# ProPrj___2025-12-14-15-46-23.net
KiCad netlist of a schematic drawn in EasyEDA Pro
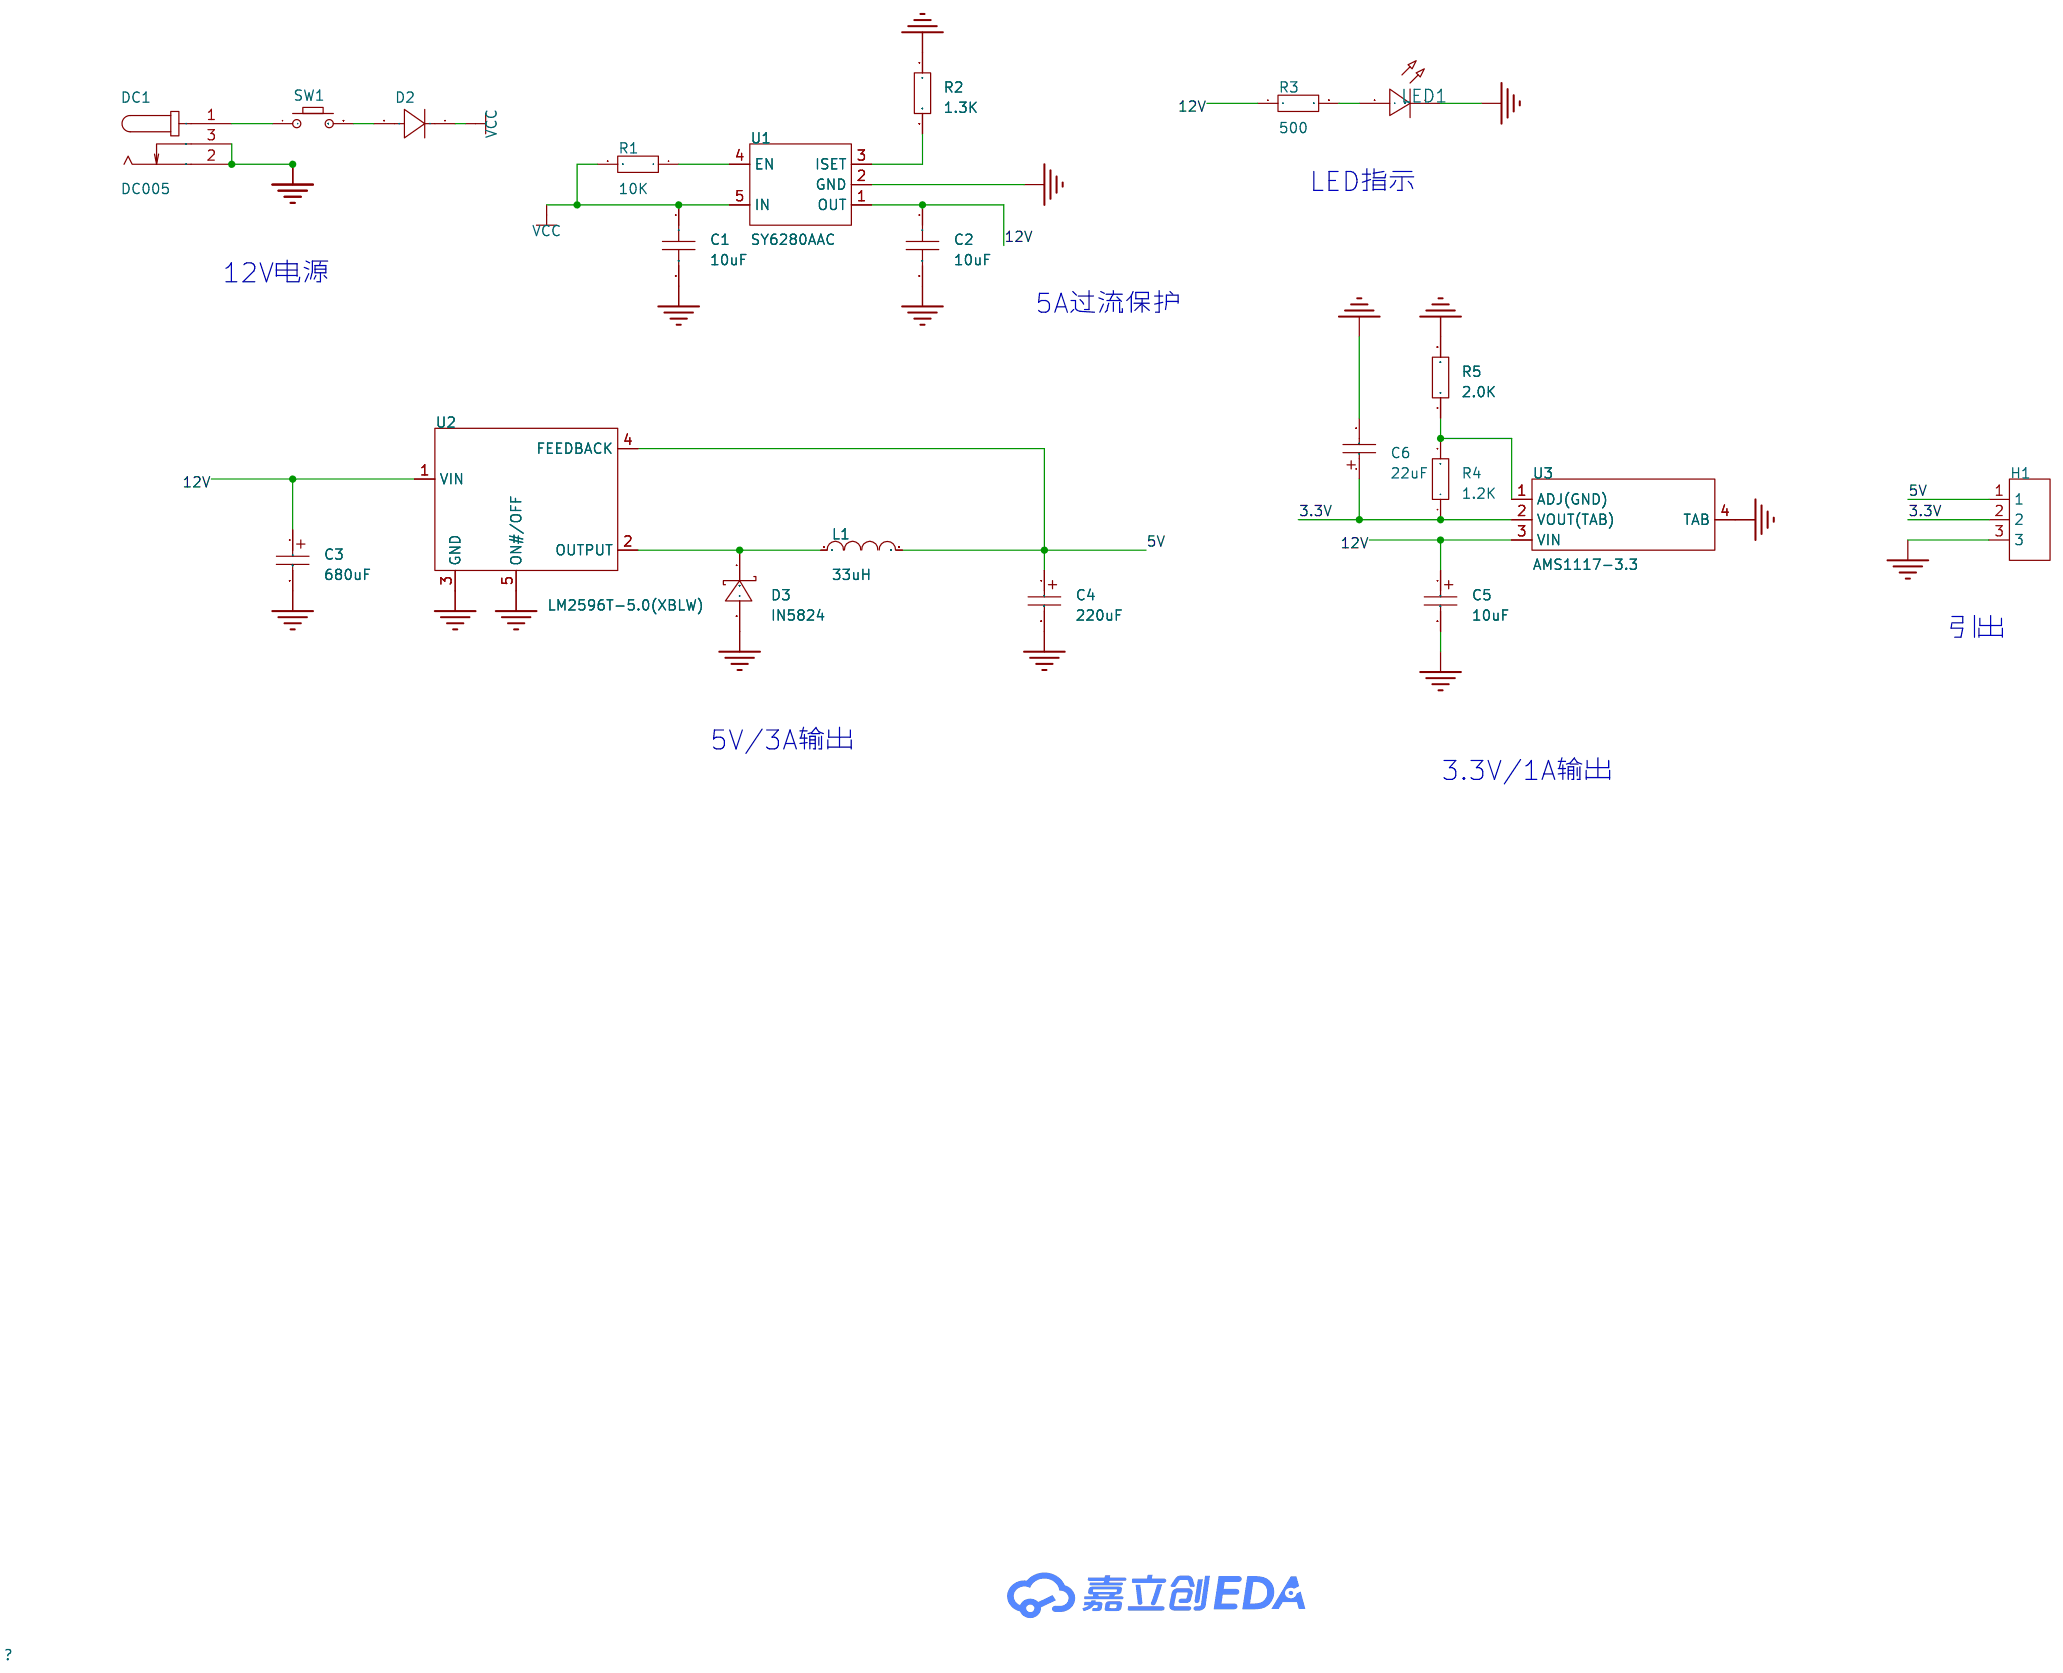
[diagram p0: schematic sheet]

(export (version "E")
  (design (tool "Eeschema 10.0.6"))
  (components
    (comp (ref "C1")
      (value "10uF")
      (footprint "easyedapro:C0603")
      (libsource (lib "easyedapro") (part "Capacitance"))
    )
    (comp (ref "C2")
      (value "10uF")
      (footprint "easyedapro:C0603")
      (libsource (lib "easyedapro") (part "Capacitance"))
    )
    (comp (ref "C3")
      (value "680uF")
      (footprint "easyedapro:C_Ele_SMD_3x5.4mm")
      (libsource (lib "easyedapro") (part "CAP"))
    )
    (comp (ref "C4")
      (value "220uF")
      (footprint "easyedapro:C_Ele_SMD_3x5.4mm")
      (libsource (lib "easyedapro") (part "CAP"))
    )
    (comp (ref "C5")
      (value "10uF")
      (footprint "easyedapro:C_Ele_SMD_3x5.4mm")
      (libsource (lib "easyedapro") (part "CAP"))
    )
    (comp (ref "C6")
      (value "22uF")
      (footprint "easyedapro:C_Ele_SMD_3x5.4mm")
      (libsource (lib "easyedapro") (part "CAP"))
    )
    (comp (ref "D2")
      (value "~")
      (footprint "easyedapro:DO_1N4007")
      (libsource (lib "easyedapro") (part "D_1N4007"))
    )
    (comp (ref "D3")
      (value "IN5824")
      (footprint "easyedapro:SMAF_L3.5-W2.6-LS4.7-RD")
      (libsource (lib "easyedapro") (part "IN5824"))
    )
    (comp (ref "DC1")
      (value "DC005")
      (footprint "easyedapro:DC-IN-TH_DC005")
      (description "连接器类型:DC电源插座;安装方式:弯插;触点内径:2mm;触点外径:6.3mm;额定电流:500mA;额定电压:12V;工作温度:-30°C~+70°C;")
      (fields (field (name "Manufacturer") "SHOU HAN(首韩)"))
      (libsource (lib "easyedapro") (part "DC005_C431533"))
    )
    (comp (ref "H1")
      (value "~")
      (footprint "easyedapro:HDR-TH_3P-P2.54-V-F")
      (libsource (lib "easyedapro") (part "PM254V-11-03-H85"))
    )
    (comp (ref "L1")
      (value "33uH")
      (footprint "easyedapro:L0603")
      (libsource (lib "easyedapro") (part "SDFL1608S100KTF"))
    )
    (comp (ref "LED1")
      (value "~")
      (footprint "easyedapro:LED_0603")
      (libsource (lib "easyedapro") (part "LED_R"))
    )
    (comp (ref "R1") (value "10K") (footprint "easyedapro:R0603") (libsource (lib "easyedapro") (part "电阻")))
    (comp (ref "R2") (value "1.3K") (footprint "easyedapro:R0603") (libsource (lib "easyedapro") (part "电阻")))
    (comp (ref "R3") (value "500") (footprint "easyedapro:R0603") (libsource (lib "easyedapro") (part "电阻")))
    (comp (ref "R4") (value "1.2K") (footprint "easyedapro:R0603") (libsource (lib "easyedapro") (part "电阻")))
    (comp (ref "R5") (value "2.0K") (footprint "easyedapro:R0603") (libsource (lib "easyedapro") (part "电阻")))
    (comp (ref "SW1")
      (value "~")
      (footprint "easyedapro:Key_TH_3.5x6x4.3")
      (libsource (lib "easyedapro") (part "Key_TH_3.5x6x4.3"))
    )
    (comp (ref "U1")
      (value "SY6280AAC")
      (footprint "easyedapro:SOT-23-5_L3.0-W1.7-P0.95-LS2.8-BR")
      (libsource (lib "easyedapro") (part "SY6280AAC_C9900003867"))
    )
    (comp (ref "U2")
      (value "LM2596T-5.0(XBLW)")
      (footprint "easyedapro:TO-220-5L_L10.2-W4.5-P1.71-L")
      (description "功能类型:降压型;工作电压:6V~40V;输出电压:5V;输出电流:3A;输出类型:固定;")
      (fields (field (name "Manufacturer") "XBLW(芯伯乐)"))
      (libsource (lib "easyedapro") (part "LM2596T-5.0(XBLW)"))
    )
    (comp (ref "U3")
      (value "AMS1117-3.3")
      (footprint "easyedapro:SOT-223-4_L6.5-W3.5-P2.30-LS7.0-BR")
      (description "输出类型:固定;工作电压:12V;输出电压:3.3V;输出电流:1A;电源纹波抑制比(PSRR):60dB@(120Hz);输出极性:正极;")
      (fields (field (name "Manufacturer") "UMW(友台半导体)"))
      (libsource (lib "easyedapro") (part "AMS1117-3.3_C347222"))
    )
  )
  (nets
    (net (code "1") (name "/3.3V") (class "Default")
      (node (ref "C6") (pin "1") (pinfunction "1_1") (pintype "input"))
      (node (ref "H1") (pin "2") (pinfunction "2_2") (pintype "unspecified"))
      (node (ref "R4") (pin "1") (pinfunction "1_1") (pintype "input"))
      (node (ref "U3") (pin "2") (pinfunction "VOUT(TAB)_2") (pintype "unspecified"))
    )
    (net (code "2") (name "/5V") (class "Default")
      (node (ref "C4") (pin "1") (pinfunction "1_1") (pintype "input"))
      (node (ref "H1") (pin "1") (pinfunction "1_1") (pintype "unspecified"))
      (node (ref "L1") (pin "2") (pinfunction "2_2") (pintype "unspecified"))
      (node (ref "U2") (pin "4") (pinfunction "FEEDBACK_4") (pintype "unspecified"))
    )
    (net (code "3") (name "/12V") (class "Default")
      (node (ref "C2") (pin "1") (pinfunction "1_1") (pintype "input"))
      (node (ref "C3") (pin "1") (pinfunction "1_1") (pintype "input"))
      (node (ref "C5") (pin "1") (pinfunction "1_1") (pintype "input"))
      (node (ref "R3") (pin "1") (pinfunction "1_1") (pintype "input"))
      (node (ref "U1") (pin "1") (pinfunction "OUT_1") (pintype "unspecified"))
      (node (ref "U2") (pin "1") (pinfunction "VIN_1") (pintype "unspecified"))
      (node (ref "U3") (pin "3") (pinfunction "VIN_3") (pintype "unspecified"))
    )
    (net (code "4") (name "GND") (class "Default")
      (node (ref "C1") (pin "2") (pinfunction "2_2") (pintype "input"))
      (node (ref "C2") (pin "2") (pinfunction "2_2") (pintype "input"))
      (node (ref "C3") (pin "2") (pinfunction "2_2") (pintype "input"))
      (node (ref "C4") (pin "2") (pinfunction "2_2") (pintype "input"))
      (node (ref "C5") (pin "2") (pinfunction "2_2") (pintype "input"))
      (node (ref "C6") (pin "2") (pinfunction "2_2") (pintype "input"))
      (node (ref "D3") (pin "2") (pinfunction "A_2") (pintype "unspecified"))
      (node (ref "DC1") (pin "2") (pinfunction "2_2") (pintype "unspecified"))
      (node (ref "DC1") (pin "3") (pinfunction "3_3") (pintype "unspecified"))
      (node (ref "H1") (pin "3") (pinfunction "3_3") (pintype "unspecified"))
      (node (ref "LED1") (pin "1") (pinfunction "C_1") (pintype "input"))
      (node (ref "R2") (pin "1") (pinfunction "1_1") (pintype "input"))
      (node (ref "R5") (pin "2") (pinfunction "2_2") (pintype "input"))
      (node (ref "U1") (pin "2") (pinfunction "GND_2") (pintype "unspecified"))
      (node (ref "U2") (pin "3") (pinfunction "GND_3") (pintype "unspecified"))
      (node (ref "U2") (pin "5") (pinfunction "ON#/OFF_5") (pintype "unspecified"))
      (node (ref "U3") (pin "4") (pinfunction "TAB_4") (pintype "unspecified"))
    )
    (net (code "5") (name "Net-(D2-A)") (class "Default")
      (node (ref "D2") (pin "2") (pinfunction "A_2") (pintype "input"))
      (node (ref "SW1") (pin "B") (pinfunction "B_B") (pintype "input"))
    )
    (net (code "6") (name "Net-(D3-C)") (class "Default")
      (node (ref "D3") (pin "1") (pinfunction "C_1") (pintype "unspecified"))
      (node (ref "L1") (pin "1") (pinfunction "1_1") (pintype "unspecified"))
      (node (ref "U2") (pin "2") (pinfunction "OUTPUT_2") (pintype "unspecified"))
    )
    (net (code "7") (name "Net-(DC1-Pad1)") (class "Default")
      (node (ref "DC1") (pin "1") (pinfunction "1_1") (pintype "unspecified"))
      (node (ref "SW1") (pin "A") (pinfunction "A_A") (pintype "input"))
    )
    (net (code "8") (name "Net-(LED1-A)") (class "Default")
      (node (ref "LED1") (pin "2") (pinfunction "A_2") (pintype "input"))
      (node (ref "R3") (pin "2") (pinfunction "2_2") (pintype "input"))
    )
    (net (code "9") (name "Net-(U1-EN)") (class "Default")
      (node (ref "R1") (pin "1") (pinfunction "1_1") (pintype "input"))
      (node (ref "U1") (pin "4") (pinfunction "EN_4") (pintype "unspecified"))
    )
    (net (code "10") (name "Net-(U1-ISET)") (class "Default")
      (node (ref "R2") (pin "2") (pinfunction "2_2") (pintype "input"))
      (node (ref "U1") (pin "3") (pinfunction "ISET_3") (pintype "unspecified"))
    )
    (net (code "11") (name "Net-(U3-ADJ(GND))") (class "Default")
      (node (ref "R4") (pin "2") (pinfunction "2_2") (pintype "input"))
      (node (ref "R5") (pin "1") (pinfunction "1_1") (pintype "input"))
      (node (ref "U3") (pin "1") (pinfunction "ADJ(GND)_1") (pintype "unspecified"))
    )
    (net (code "12") (name "VCC") (class "Default")
      (node (ref "C1") (pin "1") (pinfunction "1_1") (pintype "input"))
      (node (ref "D2") (pin "1") (pinfunction "K_1") (pintype "input"))
      (node (ref "R1") (pin "2") (pinfunction "2_2") (pintype "input"))
      (node (ref "U1") (pin "5") (pinfunction "IN_5") (pintype "unspecified"))
    )
  )
)
